# templogger_v1.net
KiCad netlist of a schematic drawn in EAGLE
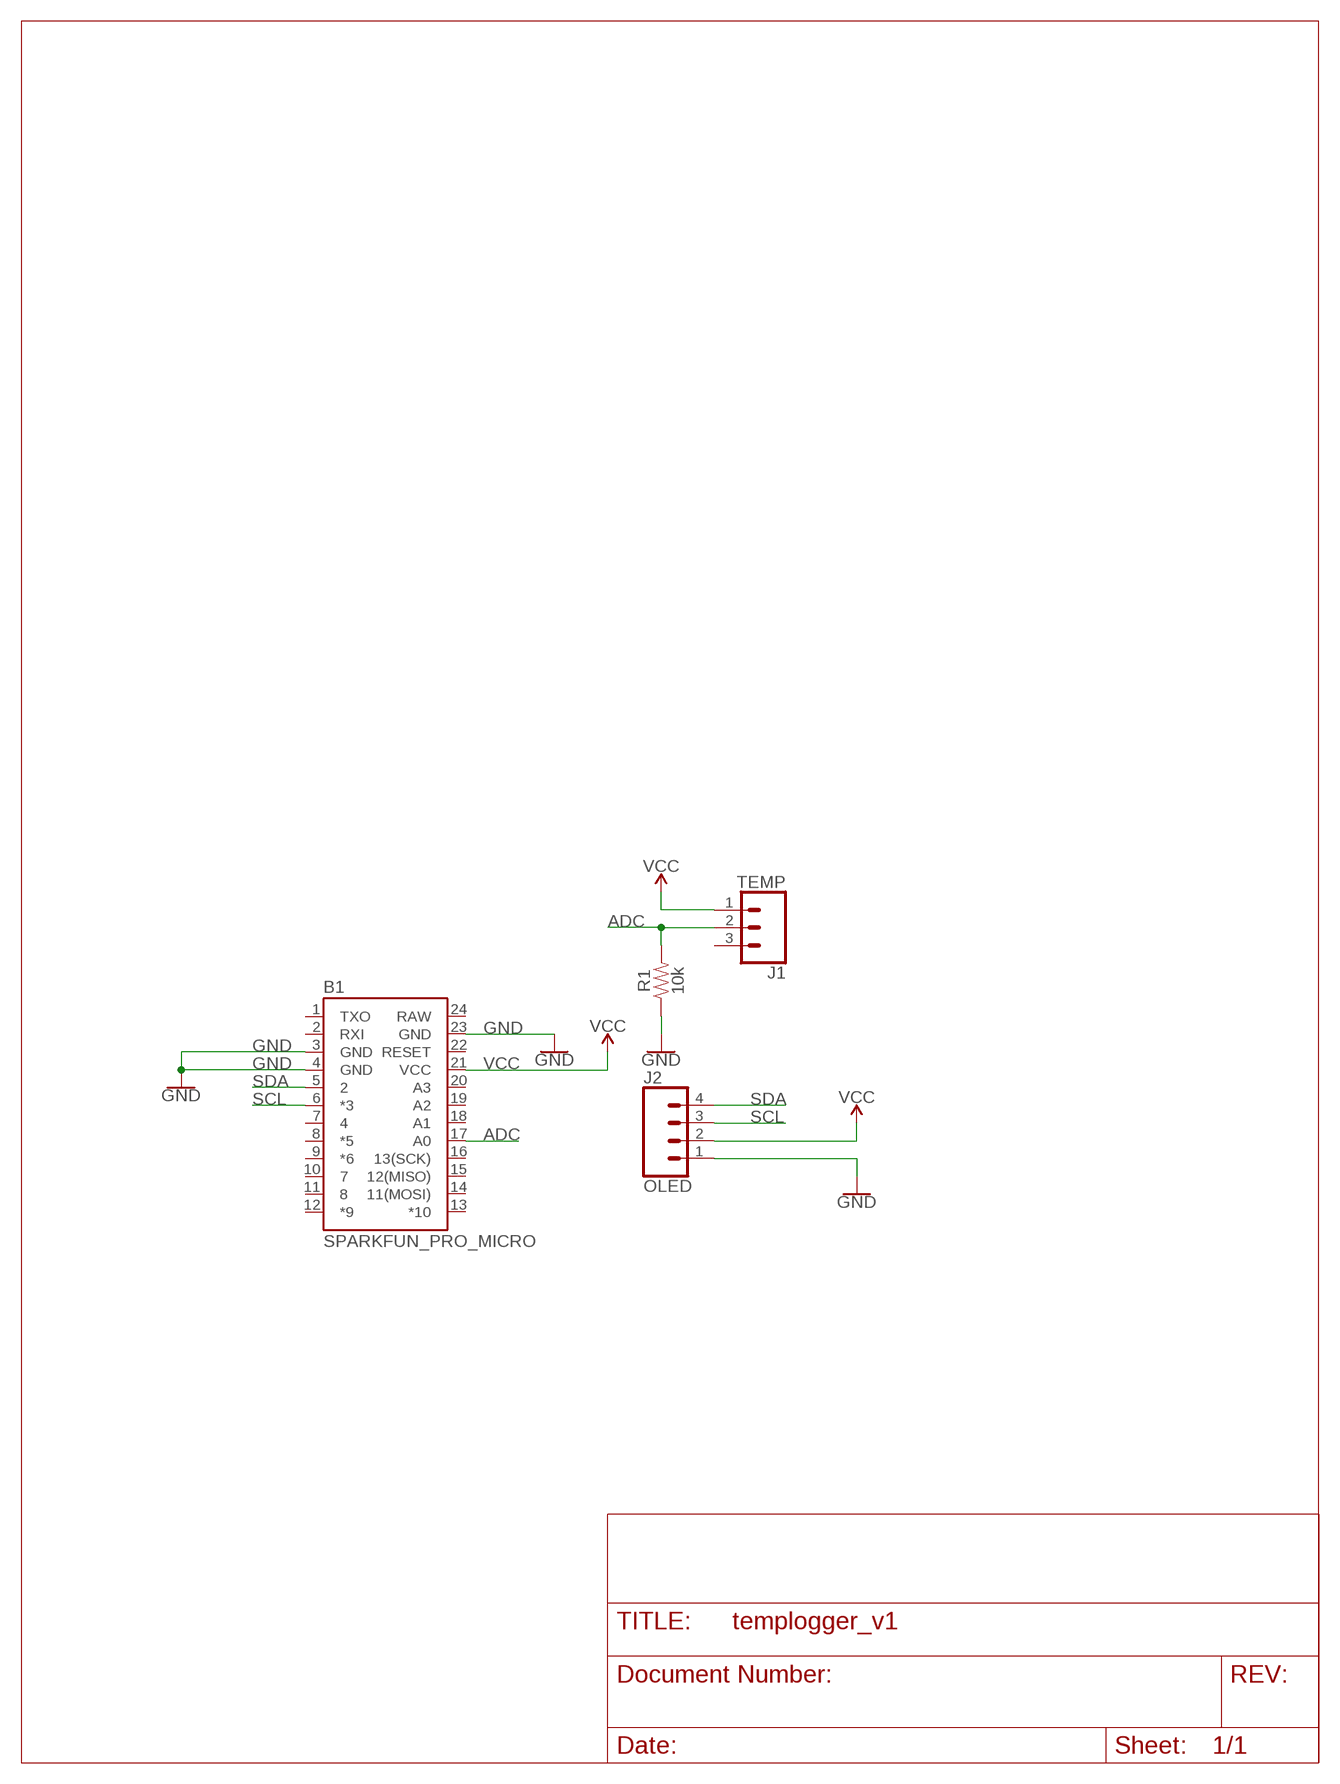
[diagram p0: schematic, sheet 1]

(export (version "E")
  (design (tool "Eeschema 10.0.6"))
  (components
    (comp (ref "B1")
      (value "SPARKFUN_PRO_MICRO")
      (footprint "eagle-import:SPARKFUN_PRO_MICRO")
      (fields (field (name "SPICEPREFIX") "X"))
      (libsource (lib "eagle-import") (part "SPARKFUN_PRO_MICRO"))
    )
    (comp (ref "J1")
      (value "TEMP")
      (footprint "eagle-import:1X03")
      (libsource (lib "eagle-import") (part "CONN_03"))
    )
    (comp (ref "J2")
      (value "OLED")
      (footprint "eagle-import:1X04")
      (libsource (lib "eagle-import") (part "CONN_04"))
    )
    (comp (ref "R1")
      (value "10k")
      (footprint "eagle-import:AXIAL-0.3")
      (libsource (lib "eagle-import") (part "10KOHM-HORIZ-1/4W-1%"))
    )
  )
  (nets
    (net (code "1") (name "/ADC") (class "Default")
      (node (ref "B1") (pin "17") (pinfunction "A0_17") (pintype "bidirectional"))
      (node (ref "J1") (pin "2") (pinfunction "2_2") (pintype "passive"))
      (node (ref "R1") (pin "P$2") (pinfunction "2_P$2") (pintype "passive"))
    )
    (net (code "2") (name "/RAW") (class "Default")
      (node (ref "B1") (pin "24") (pinfunction "RAW_24") (pintype "power_in"))
    )
    (net (code "3") (name "/SCL") (class "Default")
      (node (ref "B1") (pin "6") (pinfunction "*3_6") (pintype "bidirectional"))
      (node (ref "J2") (pin "3") (pinfunction "3_3") (pintype "passive"))
    )
    (net (code "4") (name "/SDA") (class "Default")
      (node (ref "B1") (pin "5") (pinfunction "2_5") (pintype "bidirectional"))
      (node (ref "J2") (pin "4") (pinfunction "4_4") (pintype "passive"))
    )
    (net (code "5") (name "GND") (class "Default")
      (node (ref "B1") (pin "23") (pinfunction "GND_23") (pintype "power_in"))
      (node (ref "B1") (pin "3") (pinfunction "GND_3") (pintype "power_in"))
      (node (ref "B1") (pin "4") (pinfunction "GND_4") (pintype "power_in"))
      (node (ref "J2") (pin "1") (pinfunction "1_1") (pintype "passive"))
      (node (ref "R1") (pin "P$1") (pinfunction "1_P$1") (pintype "passive"))
    )
    (net (code "6") (name "VCC") (class "Default")
      (node (ref "B1") (pin "21") (pinfunction "VCC_21") (pintype "power_in"))
      (node (ref "J1") (pin "1") (pinfunction "1_1") (pintype "passive"))
      (node (ref "J2") (pin "2") (pinfunction "2_2") (pintype "passive"))
    )
    (net (code "7") (name "unconnected-(B1-*5-Pad8)") (class "Default")
      (node (ref "B1") (pin "8") (pinfunction "*5_8") (pintype "bidirectional"))
    )
    (net (code "8") (name "unconnected-(B1-*6-Pad9)") (class "Default")
      (node (ref "B1") (pin "9") (pinfunction "*6_9") (pintype "bidirectional"))
    )
    (net (code "9") (name "unconnected-(B1-*9-Pad12)") (class "Default")
      (node (ref "B1") (pin "12") (pinfunction "*9_12") (pintype "bidirectional"))
    )
    (net (code "10") (name "unconnected-(B1-*10-Pad13)") (class "Default")
      (node (ref "B1") (pin "13") (pinfunction "*10_13") (pintype "bidirectional"))
    )
    (net (code "11") (name "unconnected-(B1-4-Pad7)") (class "Default")
      (node (ref "B1") (pin "7") (pinfunction "4_7") (pintype "bidirectional"))
    )
    (net (code "12") (name "unconnected-(B1-7-Pad10)") (class "Default")
      (node (ref "B1") (pin "10") (pinfunction "7_10") (pintype "bidirectional"))
    )
    (net (code "13") (name "unconnected-(B1-8-Pad11)") (class "Default")
      (node (ref "B1") (pin "11") (pinfunction "8_11") (pintype "bidirectional"))
    )
    (net (code "14") (name "unconnected-(B1-11(MOSI)-Pad14)") (class "Default")
      (node (ref "B1") (pin "14") (pinfunction "11(MOSI)_14") (pintype "bidirectional"))
    )
    (net (code "15") (name "unconnected-(B1-12(MISO)-Pad15)") (class "Default")
      (node (ref "B1") (pin "15") (pinfunction "12(MISO)_15") (pintype "bidirectional"))
    )
    (net (code "16") (name "unconnected-(B1-13(SCK)-Pad16)") (class "Default")
      (node (ref "B1") (pin "16") (pinfunction "13(SCK)_16") (pintype "bidirectional"))
    )
    (net (code "17") (name "unconnected-(B1-A1-Pad18)") (class "Default")
      (node (ref "B1") (pin "18") (pinfunction "A1_18") (pintype "bidirectional"))
    )
    (net (code "18") (name "unconnected-(B1-A2-Pad19)") (class "Default")
      (node (ref "B1") (pin "19") (pinfunction "A2_19") (pintype "bidirectional"))
    )
    (net (code "19") (name "unconnected-(B1-A3-Pad20)") (class "Default")
      (node (ref "B1") (pin "20") (pinfunction "A3_20") (pintype "bidirectional"))
    )
    (net (code "20") (name "unconnected-(B1-RESET-Pad22)") (class "Default")
      (node (ref "B1") (pin "22") (pinfunction "RESET_22") (pintype "bidirectional"))
    )
    (net (code "21") (name "unconnected-(B1-RXI-Pad2)") (class "Default")
      (node (ref "B1") (pin "2") (pinfunction "RXI_2") (pintype "bidirectional"))
    )
    (net (code "22") (name "unconnected-(B1-TXO-Pad1)") (class "Default")
      (node (ref "B1") (pin "1") (pinfunction "TXO_1") (pintype "bidirectional"))
    )
    (net (code "23") (name "unconnected-(J1-Pad3)") (class "Default")
      (node (ref "J1") (pin "3") (pinfunction "3_3") (pintype "passive"))
    )
  )
)
